# atmel_modular_expansion.net
KiCad netlist of a schematic drawn in EAGLE
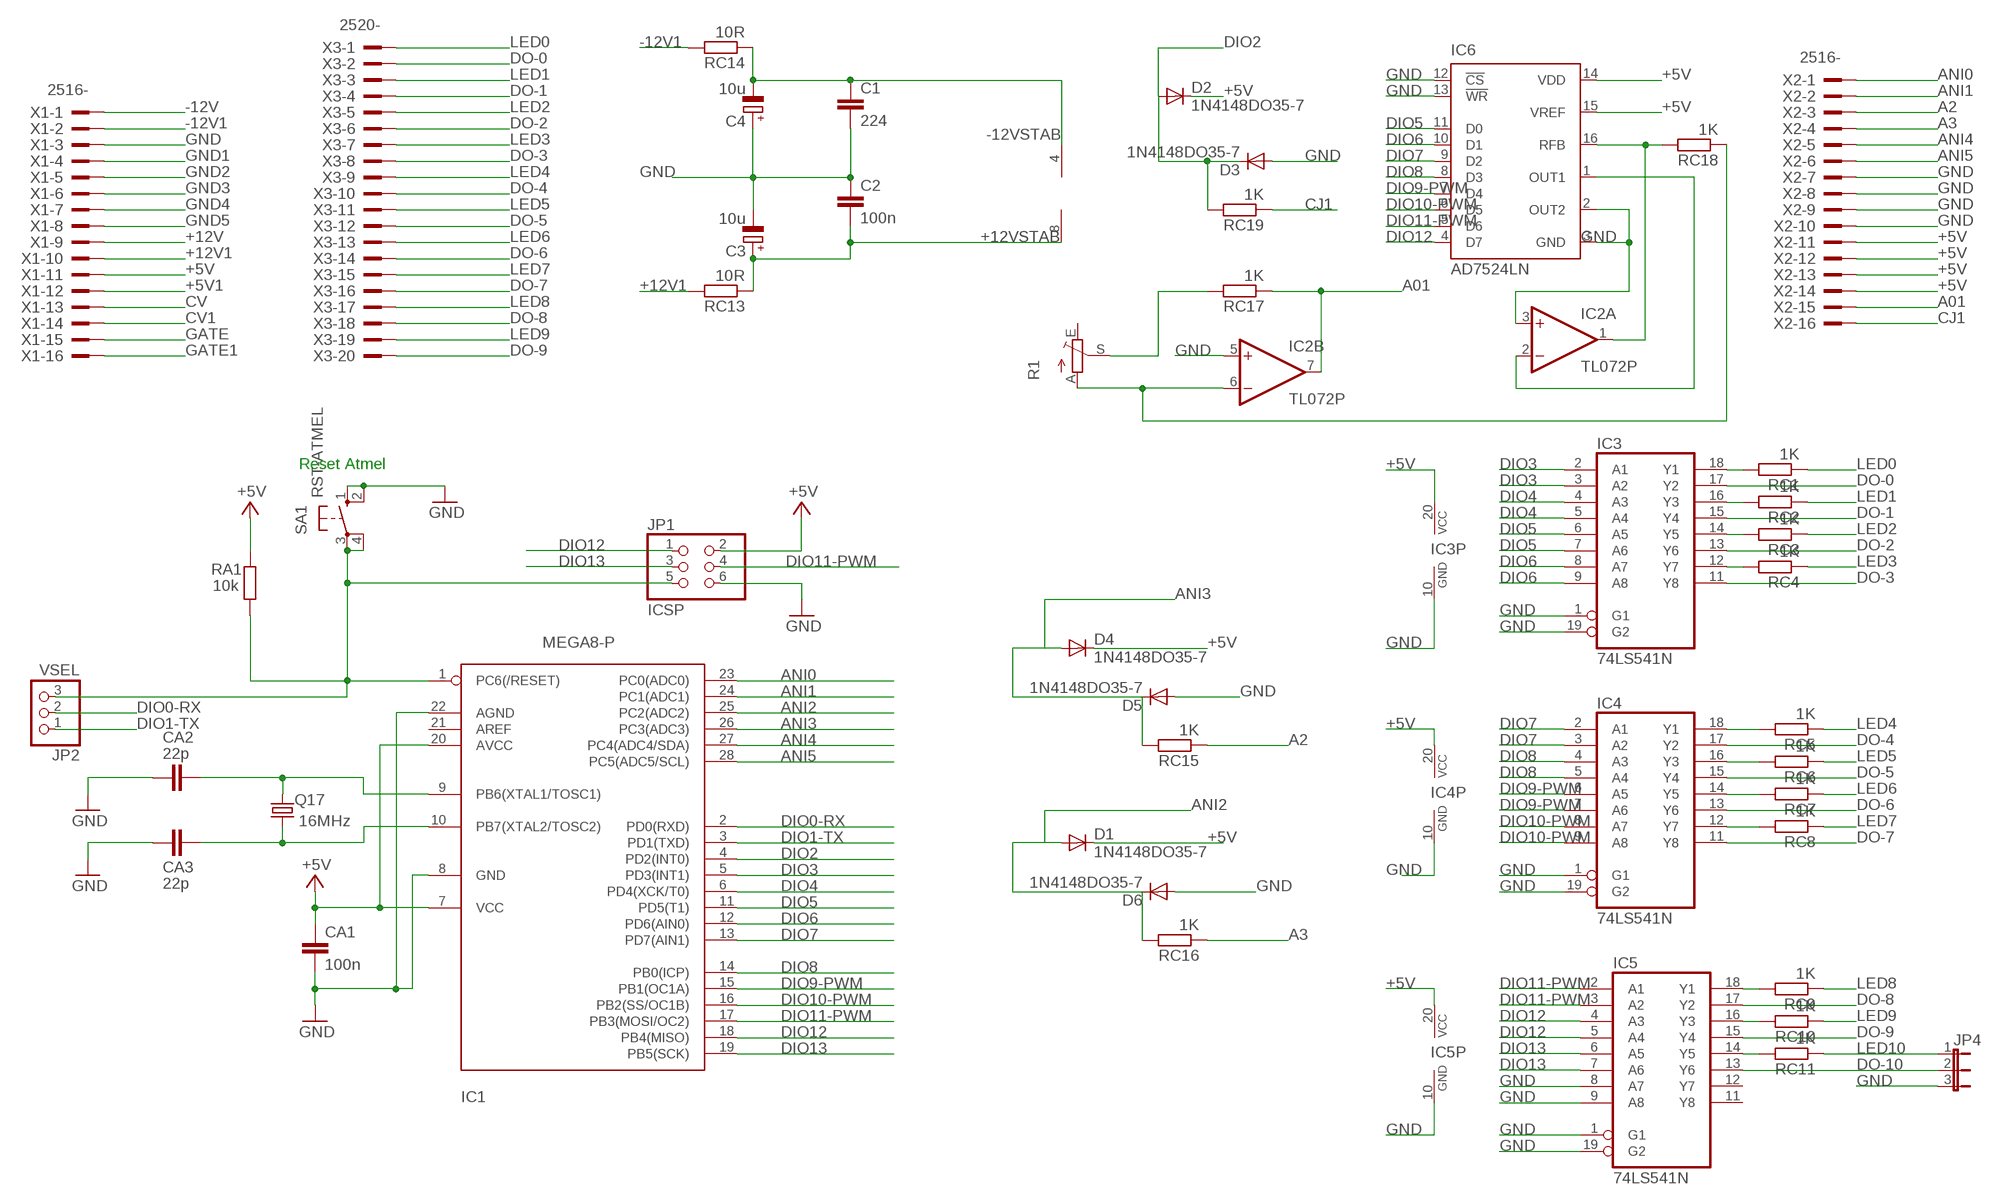
[diagram p0: schematic, sheet 1]

(export (version "E")
  (design (tool "Eeschema 10.0.6"))
  (components
    (comp (ref "C1")
      (value "224")
      (footprint "eagle-import:C050-025X075")
      (libsource (lib "eagle-import") (part "C-EU050-025X075"))
    )
    (comp (ref "C2")
      (value "100n")
      (footprint "eagle-import:C050-025X075")
      (libsource (lib "eagle-import") (part "C-EU050-025X075"))
    )
    (comp (ref "C3")
      (value "10u")
      (footprint "eagle-import:E2,5-7")
      (libsource (lib "eagle-import") (part "CPOL-EUE2.5-7"))
    )
    (comp (ref "C4")
      (value "10u")
      (footprint "eagle-import:E2,5-7")
      (libsource (lib "eagle-import") (part "CPOL-EUE2.5-7"))
    )
    (comp (ref "CA1")
      (value "100n")
      (footprint "eagle-import:C050-025X075")
      (libsource (lib "eagle-import") (part "C-EU050-025X075"))
    )
    (comp (ref "CA2")
      (value "22p")
      (footprint "eagle-import:C050-025X075")
      (libsource (lib "eagle-import") (part "C-EU050-025X075"))
    )
    (comp (ref "CA3")
      (value "22p")
      (footprint "eagle-import:C050-025X075")
      (libsource (lib "eagle-import") (part "C-EU050-025X075"))
    )
    (comp (ref "D1")
      (value "1N4148DO35-7")
      (footprint "eagle-import:DO35-7")
      (libsource (lib "eagle-import") (part "1N4148DO35-7"))
    )
    (comp (ref "D2")
      (value "1N4148DO35-7")
      (footprint "eagle-import:DO35-7")
      (libsource (lib "eagle-import") (part "1N4148DO35-7"))
    )
    (comp (ref "D3")
      (value "1N4148DO35-7")
      (footprint "eagle-import:DO35-7")
      (libsource (lib "eagle-import") (part "1N4148DO35-7"))
    )
    (comp (ref "D4")
      (value "1N4148DO35-7")
      (footprint "eagle-import:DO35-7")
      (libsource (lib "eagle-import") (part "1N4148DO35-7"))
    )
    (comp (ref "D5")
      (value "1N4148DO35-7")
      (footprint "eagle-import:DO35-7")
      (libsource (lib "eagle-import") (part "1N4148DO35-7"))
    )
    (comp (ref "D6")
      (value "1N4148DO35-7")
      (footprint "eagle-import:DO35-7")
      (libsource (lib "eagle-import") (part "1N4148DO35-7"))
    )
    (comp (ref "IC1")
      (value "MEGA8-P")
      (footprint "eagle-import:DIL28-3")
      (libsource (lib "eagle-import") (part "MEGA8-P"))
    )
    (comp (ref "IC2")
      (value "TL072P")
      (footprint "eagle-import:DIL08")
      (libsource (lib "eagle-import") (part "TL072P"))
    )
    (comp (ref "IC3")
      (value "74LS541N")
      (footprint "eagle-import:DIL20")
      (libsource (lib "eagle-import") (part "74541NLS"))
    )
    (comp (ref "IC4")
      (value "74LS541N")
      (footprint "eagle-import:DIL20")
      (libsource (lib "eagle-import") (part "74541NLS"))
    )
    (comp (ref "IC5")
      (value "74LS541N")
      (footprint "eagle-import:DIL20")
      (libsource (lib "eagle-import") (part "74541NLS"))
    )
    (comp (ref "IC6")
      (value "AD7524LN")
      (footprint "eagle-import:DIL16")
      (fields (field (name "MF") "ALTERA CORPORATION") (field (name "MPN") "AD7524LNZ"))
      (libsource (lib "eagle-import") (part "AD7524NL"))
    )
    (comp (ref "JP1")
      (value "ICSP")
      (footprint "eagle-import:2X03")
      (libsource (lib "eagle-import") (part "PINHD-2X3"))
    )
    (comp (ref "JP2")
      (value "VSEL")
      (footprint "eagle-import:1X03")
      (libsource (lib "eagle-import") (part "PINHD-1X3"))
    )
    (comp (ref "JP4")
      (value "JP2E")
      (footprint "eagle-import:JP2")
      (libsource (lib "eagle-import") (part "JP2E"))
    )
    (comp (ref "Q17")
      (value "16MHz")
      (footprint "eagle-import:HC49_S")
      (libsource (lib "eagle-import") (part "CRYSTALHC49S"))
    )
    (comp (ref "R1")
      (value "TRIM_EU-B64Y")
      (footprint "eagle-import:B64Y")
      (libsource (lib "eagle-import") (part "TRIM_EU-B64Y"))
    )
    (comp (ref "RA1")
      (value "10k")
      (footprint "eagle-import:0207_10")
      (libsource (lib "eagle-import") (part "R-EU_0207/10"))
    )
    (comp (ref "RC1")
      (value "1K")
      (footprint "eagle-import:0207_10")
      (libsource (lib "eagle-import") (part "R-EU_0207/10"))
    )
    (comp (ref "RC2")
      (value "1K")
      (footprint "eagle-import:0207_10")
      (libsource (lib "eagle-import") (part "R-EU_0207/10"))
    )
    (comp (ref "RC3")
      (value "1K")
      (footprint "eagle-import:0207_10")
      (libsource (lib "eagle-import") (part "R-EU_0207/10"))
    )
    (comp (ref "RC4")
      (value "1K")
      (footprint "eagle-import:0207_10")
      (libsource (lib "eagle-import") (part "R-EU_0207/10"))
    )
    (comp (ref "RC5")
      (value "1K")
      (footprint "eagle-import:0207_10")
      (libsource (lib "eagle-import") (part "R-EU_0207/10"))
    )
    (comp (ref "RC6")
      (value "1K")
      (footprint "eagle-import:0207_10")
      (libsource (lib "eagle-import") (part "R-EU_0207/10"))
    )
    (comp (ref "RC7")
      (value "1K")
      (footprint "eagle-import:0207_10")
      (libsource (lib "eagle-import") (part "R-EU_0207/10"))
    )
    (comp (ref "RC8")
      (value "1K")
      (footprint "eagle-import:0207_10")
      (libsource (lib "eagle-import") (part "R-EU_0207/10"))
    )
    (comp (ref "RC9")
      (value "1K")
      (footprint "eagle-import:0207_10")
      (libsource (lib "eagle-import") (part "R-EU_0207/10"))
    )
    (comp (ref "RC10")
      (value "1K")
      (footprint "eagle-import:0207_10")
      (libsource (lib "eagle-import") (part "R-EU_0207/10"))
    )
    (comp (ref "RC11")
      (value "1K")
      (footprint "eagle-import:0207_10")
      (libsource (lib "eagle-import") (part "R-EU_0207/10"))
    )
    (comp (ref "RC13")
      (value "10R")
      (footprint "eagle-import:0207_10")
      (libsource (lib "eagle-import") (part "R-EU_0207/10"))
    )
    (comp (ref "RC14")
      (value "10R")
      (footprint "eagle-import:0207_10")
      (libsource (lib "eagle-import") (part "R-EU_0207/10"))
    )
    (comp (ref "RC15")
      (value "1K")
      (footprint "eagle-import:0207_10")
      (libsource (lib "eagle-import") (part "R-EU_0207/10"))
    )
    (comp (ref "RC16")
      (value "1K")
      (footprint "eagle-import:0207_10")
      (libsource (lib "eagle-import") (part "R-EU_0207/10"))
    )
    (comp (ref "RC17")
      (value "1K")
      (footprint "eagle-import:0207_10")
      (libsource (lib "eagle-import") (part "R-EU_0207/10"))
    )
    (comp (ref "RC18")
      (value "1K")
      (footprint "eagle-import:0207_10")
      (libsource (lib "eagle-import") (part "R-EU_0207/10"))
    )
    (comp (ref "RC19")
      (value "1K")
      (footprint "eagle-import:0207_10")
      (libsource (lib "eagle-import") (part "R-EU_0207/10"))
    )
    (comp (ref "SA1")
      (value "RST-ATMEL")
      (footprint "eagle-import:B3F-10XX")
      (libsource (lib "eagle-import") (part "10-XX"))
    )
    (comp (ref "X1")
      (value "2516-")
      (footprint "eagle-import:PAK100_2500-16")
      (libsource (lib "eagle-import") (part "2516-"))
    )
    (comp (ref "X2")
      (value "2516-")
      (footprint "eagle-import:PAK100_2500-16")
      (libsource (lib "eagle-import") (part "2516-"))
    )
    (comp (ref "X3")
      (value "2520-")
      (footprint "eagle-import:PAK100_2500-20")
      (libsource (lib "eagle-import") (part "2520-"))
    )
  )
  (nets
    (net (code "1") (name "+5V") (class "Default")
      (node (ref "CA1") (pin "1") (pinfunction "1_1") (pintype "passive"))
      (node (ref "D1") (pin "C") (pinfunction "C_C") (pintype "passive"))
      (node (ref "D2") (pin "C") (pinfunction "C_C") (pintype "passive"))
      (node (ref "D4") (pin "C") (pinfunction "C_C") (pintype "passive"))
      (node (ref "IC1") (pin "20") (pinfunction "AVCC_20") (pintype "power_in"))
      (node (ref "IC1") (pin "7") (pinfunction "VCC_7") (pintype "power_in"))
      (node (ref "IC3") (pin "20") (pinfunction "VCC_20") (pintype "power_in"))
      (node (ref "IC4") (pin "20") (pinfunction "VCC_20") (pintype "power_in"))
      (node (ref "IC5") (pin "20") (pinfunction "VCC_20") (pintype "power_in"))
      (node (ref "IC6") (pin "14") (pinfunction "VDD_14") (pintype "power_in"))
      (node (ref "IC6") (pin "15") (pinfunction "VREF_15") (pintype "input"))
      (node (ref "JP1") (pin "2") (pinfunction "2_2") (pintype "passive"))
      (node (ref "RA1") (pin "1") (pinfunction "1_1") (pintype "passive"))
      (node (ref "X1") (pin "11") (pinfunction "KL_11") (pintype "passive"))
      (node (ref "X2") (pin "11") (pinfunction "KL_11") (pintype "passive"))
      (node (ref "X2") (pin "12") (pinfunction "KL_12") (pintype "passive"))
      (node (ref "X2") (pin "13") (pinfunction "KL_13") (pintype "passive"))
      (node (ref "X2") (pin "14") (pinfunction "KL_14") (pintype "passive"))
    )
    (net (code "2") (name "/+5V1") (class "Default")
      (node (ref "X1") (pin "12") (pinfunction "KL_12") (pintype "passive"))
    )
    (net (code "3") (name "/+12V") (class "Default")
      (node (ref "X1") (pin "9") (pinfunction "KL_9") (pintype "passive"))
    )
    (net (code "4") (name "/+12V1") (class "Default")
      (node (ref "RC13") (pin "2") (pinfunction "2_2") (pintype "passive"))
      (node (ref "X1") (pin "10") (pinfunction "KL_10") (pintype "passive"))
    )
    (net (code "5") (name "/+12VSTAB") (class "Default")
      (node (ref "C2") (pin "2") (pinfunction "2_2") (pintype "passive"))
      (node (ref "C3") (pin "+") (pinfunction "+_+") (pintype "passive"))
      (node (ref "IC2") (pin "8") (pinfunction "V+_8") (pintype "power_in"))
      (node (ref "RC13") (pin "1") (pinfunction "1_1") (pintype "passive"))
    )
    (net (code "6") (name "/-12V") (class "Default")
      (node (ref "X1") (pin "1") (pinfunction "KL_1") (pintype "passive"))
    )
    (net (code "7") (name "/-12V1") (class "Default")
      (node (ref "RC14") (pin "2") (pinfunction "2_2") (pintype "passive"))
      (node (ref "X1") (pin "2") (pinfunction "KL_2") (pintype "passive"))
    )
    (net (code "8") (name "/-12VSTAB") (class "Default")
      (node (ref "C1") (pin "1") (pinfunction "1_1") (pintype "passive"))
      (node (ref "C4") (pin "-") (pinfunction "-_-") (pintype "passive"))
      (node (ref "IC2") (pin "4") (pinfunction "V-_4") (pintype "power_in"))
      (node (ref "RC14") (pin "1") (pinfunction "1_1") (pintype "passive"))
    )
    (net (code "9") (name "/A01") (class "Default")
      (node (ref "IC2") (pin "7") (pinfunction "OUT_7") (pintype "output"))
      (node (ref "RC17") (pin "1") (pinfunction "1_1") (pintype "passive"))
      (node (ref "X2") (pin "15") (pinfunction "KL_15") (pintype "passive"))
    )
    (net (code "10") (name "/A2") (class "Default")
      (node (ref "RC15") (pin "1") (pinfunction "1_1") (pintype "passive"))
      (node (ref "X2") (pin "3") (pinfunction "KL_3") (pintype "passive"))
    )
    (net (code "11") (name "/A3") (class "Default")
      (node (ref "RC16") (pin "1") (pinfunction "1_1") (pintype "passive"))
      (node (ref "X2") (pin "4") (pinfunction "KL_4") (pintype "passive"))
    )
    (net (code "12") (name "/ANI0") (class "Default")
      (node (ref "IC1") (pin "23") (pinfunction "PC0(ADC0)_23") (pintype "bidirectional"))
      (node (ref "X2") (pin "1") (pinfunction "KL_1") (pintype "passive"))
    )
    (net (code "13") (name "/ANI1") (class "Default")
      (node (ref "IC1") (pin "24") (pinfunction "PC1(ADC1)_24") (pintype "bidirectional"))
      (node (ref "X2") (pin "2") (pinfunction "KL_2") (pintype "passive"))
    )
    (net (code "14") (name "/ANI2") (class "Default")
      (node (ref "D1") (pin "A") (pinfunction "A_A") (pintype "passive"))
      (node (ref "D6") (pin "C") (pinfunction "C_C") (pintype "passive"))
      (node (ref "IC1") (pin "25") (pinfunction "PC2(ADC2)_25") (pintype "bidirectional"))
      (node (ref "RC16") (pin "2") (pinfunction "2_2") (pintype "passive"))
    )
    (net (code "15") (name "/ANI3") (class "Default")
      (node (ref "D4") (pin "A") (pinfunction "A_A") (pintype "passive"))
      (node (ref "D5") (pin "C") (pinfunction "C_C") (pintype "passive"))
      (node (ref "IC1") (pin "26") (pinfunction "PC3(ADC3)_26") (pintype "bidirectional"))
      (node (ref "RC15") (pin "2") (pinfunction "2_2") (pintype "passive"))
    )
    (net (code "16") (name "/ANI4") (class "Default")
      (node (ref "IC1") (pin "27") (pinfunction "PC4(ADC4/SDA)_27") (pintype "bidirectional"))
      (node (ref "X2") (pin "5") (pinfunction "KL_5") (pintype "passive"))
    )
    (net (code "17") (name "/ANI5") (class "Default")
      (node (ref "IC1") (pin "28") (pinfunction "PC5(ADC5/SCL)_28") (pintype "bidirectional"))
      (node (ref "X2") (pin "6") (pinfunction "KL_6") (pintype "passive"))
    )
    (net (code "18") (name "/CJ1") (class "Default")
      (node (ref "RC19") (pin "1") (pinfunction "1_1") (pintype "passive"))
      (node (ref "X2") (pin "16") (pinfunction "KL_16") (pintype "passive"))
    )
    (net (code "19") (name "/CV") (class "Default")
      (node (ref "X1") (pin "13") (pinfunction "KL_13") (pintype "passive"))
    )
    (net (code "20") (name "/CV1") (class "Default")
      (node (ref "X1") (pin "14") (pinfunction "KL_14") (pintype "passive"))
    )
    (net (code "21") (name "/DIO0-RX") (class "Default")
      (node (ref "IC1") (pin "2") (pinfunction "PD0(RXD)_2") (pintype "bidirectional"))
      (node (ref "JP2") (pin "2") (pinfunction "2_2") (pintype "passive"))
    )
    (net (code "22") (name "/DIO1-TX") (class "Default")
      (node (ref "IC1") (pin "3") (pinfunction "PD1(TXD)_3") (pintype "bidirectional"))
      (node (ref "JP2") (pin "1") (pinfunction "1_1") (pintype "passive"))
    )
    (net (code "23") (name "/DIO2") (class "Default")
      (node (ref "D2") (pin "A") (pinfunction "A_A") (pintype "passive"))
      (node (ref "D3") (pin "C") (pinfunction "C_C") (pintype "passive"))
      (node (ref "IC1") (pin "4") (pinfunction "PD2(INT0)_4") (pintype "bidirectional"))
      (node (ref "RC19") (pin "2") (pinfunction "2_2") (pintype "passive"))
    )
    (net (code "24") (name "/DIO3") (class "Default")
      (node (ref "IC1") (pin "5") (pinfunction "PD3(INT1)_5") (pintype "bidirectional"))
      (node (ref "IC3") (pin "2") (pinfunction "A1_2") (pintype "input"))
      (node (ref "IC3") (pin "3") (pinfunction "A2_3") (pintype "input"))
    )
    (net (code "25") (name "/DIO4") (class "Default")
      (node (ref "IC1") (pin "6") (pinfunction "PD4(XCK/T0)_6") (pintype "bidirectional"))
      (node (ref "IC3") (pin "4") (pinfunction "A3_4") (pintype "input"))
      (node (ref "IC3") (pin "5") (pinfunction "A4_5") (pintype "input"))
    )
    (net (code "26") (name "/DIO5") (class "Default")
      (node (ref "IC1") (pin "11") (pinfunction "PD5(T1)_11") (pintype "bidirectional"))
      (node (ref "IC3") (pin "6") (pinfunction "A5_6") (pintype "input"))
      (node (ref "IC3") (pin "7") (pinfunction "A6_7") (pintype "input"))
      (node (ref "IC6") (pin "11") (pinfunction "D0_11") (pintype "input"))
    )
    (net (code "27") (name "/DIO6") (class "Default")
      (node (ref "IC1") (pin "12") (pinfunction "PD6(AIN0)_12") (pintype "bidirectional"))
      (node (ref "IC3") (pin "8") (pinfunction "A7_8") (pintype "input"))
      (node (ref "IC3") (pin "9") (pinfunction "A8_9") (pintype "input"))
      (node (ref "IC6") (pin "10") (pinfunction "D1_10") (pintype "input"))
    )
    (net (code "28") (name "/DIO7") (class "Default")
      (node (ref "IC1") (pin "13") (pinfunction "PD7(AIN1)_13") (pintype "bidirectional"))
      (node (ref "IC4") (pin "2") (pinfunction "A1_2") (pintype "input"))
      (node (ref "IC4") (pin "3") (pinfunction "A2_3") (pintype "input"))
      (node (ref "IC6") (pin "9") (pinfunction "D2_9") (pintype "input"))
    )
    (net (code "29") (name "/DIO8") (class "Default")
      (node (ref "IC1") (pin "14") (pinfunction "PB0(ICP)_14") (pintype "bidirectional"))
      (node (ref "IC4") (pin "4") (pinfunction "A3_4") (pintype "input"))
      (node (ref "IC4") (pin "5") (pinfunction "A4_5") (pintype "input"))
      (node (ref "IC6") (pin "8") (pinfunction "D3_8") (pintype "input"))
    )
    (net (code "30") (name "/DIO9-PWM") (class "Default")
      (node (ref "IC1") (pin "15") (pinfunction "PB1(OC1A)_15") (pintype "bidirectional"))
      (node (ref "IC4") (pin "6") (pinfunction "A5_6") (pintype "input"))
      (node (ref "IC4") (pin "7") (pinfunction "A6_7") (pintype "input"))
      (node (ref "IC6") (pin "7") (pinfunction "D4_7") (pintype "input"))
    )
    (net (code "31") (name "/DIO10-PWM") (class "Default")
      (node (ref "IC1") (pin "16") (pinfunction "PB2(SS/OC1B)_16") (pintype "bidirectional"))
      (node (ref "IC4") (pin "8") (pinfunction "A7_8") (pintype "input"))
      (node (ref "IC4") (pin "9") (pinfunction "A8_9") (pintype "input"))
      (node (ref "IC6") (pin "6") (pinfunction "D5_6") (pintype "input"))
    )
    (net (code "32") (name "/DIO11-PWM") (class "Default")
      (node (ref "IC1") (pin "17") (pinfunction "PB3(MOSI/OC2)_17") (pintype "bidirectional"))
      (node (ref "IC5") (pin "2") (pinfunction "A1_2") (pintype "input"))
      (node (ref "IC5") (pin "3") (pinfunction "A2_3") (pintype "input"))
      (node (ref "IC6") (pin "5") (pinfunction "D6_5") (pintype "input"))
      (node (ref "JP1") (pin "4") (pinfunction "4_4") (pintype "passive"))
    )
    (net (code "33") (name "/DIO12") (class "Default")
      (node (ref "IC1") (pin "18") (pinfunction "PB4(MISO)_18") (pintype "bidirectional"))
      (node (ref "IC5") (pin "4") (pinfunction "A3_4") (pintype "input"))
      (node (ref "IC5") (pin "5") (pinfunction "A4_5") (pintype "input"))
      (node (ref "IC6") (pin "4") (pinfunction "D7_4") (pintype "input"))
      (node (ref "JP1") (pin "1") (pinfunction "1_1") (pintype "passive"))
    )
    (net (code "34") (name "/DIO13") (class "Default")
      (node (ref "IC1") (pin "19") (pinfunction "PB5(SCK)_19") (pintype "bidirectional"))
      (node (ref "IC5") (pin "6") (pinfunction "A5_6") (pintype "input"))
      (node (ref "IC5") (pin "7") (pinfunction "A6_7") (pintype "input"))
      (node (ref "JP1") (pin "3") (pinfunction "3_3") (pintype "passive"))
    )
    (net (code "35") (name "/DO-0") (class "Default")
      (node (ref "IC3") (pin "17") (pinfunction "Y2_17") (pintype "tri_state"))
      (node (ref "X3") (pin "2") (pinfunction "KL_2") (pintype "passive"))
    )
    (net (code "36") (name "/DO-1") (class "Default")
      (node (ref "IC3") (pin "15") (pinfunction "Y4_15") (pintype "tri_state"))
      (node (ref "X3") (pin "4") (pinfunction "KL_4") (pintype "passive"))
    )
    (net (code "37") (name "/DO-2") (class "Default")
      (node (ref "IC3") (pin "13") (pinfunction "Y6_13") (pintype "tri_state"))
      (node (ref "X3") (pin "6") (pinfunction "KL_6") (pintype "passive"))
    )
    (net (code "38") (name "/DO-3") (class "Default")
      (node (ref "IC3") (pin "11") (pinfunction "Y8_11") (pintype "tri_state"))
      (node (ref "X3") (pin "8") (pinfunction "KL_8") (pintype "passive"))
    )
    (net (code "39") (name "/DO-4") (class "Default")
      (node (ref "IC4") (pin "17") (pinfunction "Y2_17") (pintype "tri_state"))
      (node (ref "X3") (pin "10") (pinfunction "KL_10") (pintype "passive"))
    )
    (net (code "40") (name "/DO-5") (class "Default")
      (node (ref "IC4") (pin "15") (pinfunction "Y4_15") (pintype "tri_state"))
      (node (ref "X3") (pin "12") (pinfunction "KL_12") (pintype "passive"))
    )
    (net (code "41") (name "/DO-6") (class "Default")
      (node (ref "IC4") (pin "13") (pinfunction "Y6_13") (pintype "tri_state"))
      (node (ref "X3") (pin "14") (pinfunction "KL_14") (pintype "passive"))
    )
    (net (code "42") (name "/DO-7") (class "Default")
      (node (ref "IC4") (pin "11") (pinfunction "Y8_11") (pintype "tri_state"))
      (node (ref "X3") (pin "16") (pinfunction "KL_16") (pintype "passive"))
    )
    (net (code "43") (name "/DO-8") (class "Default")
      (node (ref "IC5") (pin "17") (pinfunction "Y2_17") (pintype "tri_state"))
      (node (ref "X3") (pin "18") (pinfunction "KL_18") (pintype "passive"))
    )
    (net (code "44") (name "/DO-9") (class "Default")
      (node (ref "IC5") (pin "15") (pinfunction "Y4_15") (pintype "tri_state"))
      (node (ref "X3") (pin "20") (pinfunction "KL_20") (pintype "passive"))
    )
    (net (code "45") (name "/DO-10") (class "Default")
      (node (ref "IC5") (pin "13") (pinfunction "Y6_13") (pintype "tri_state"))
      (node (ref "JP4") (pin "2") (pinfunction "2_2") (pintype "passive"))
    )
    (net (code "46") (name "/GATE") (class "Default")
      (node (ref "X1") (pin "15") (pinfunction "KL_15") (pintype "passive"))
    )
    (net (code "47") (name "/GATE1") (class "Default")
      (node (ref "X1") (pin "16") (pinfunction "KL_16") (pintype "passive"))
    )
    (net (code "48") (name "/GND1") (class "Default")
      (node (ref "X1") (pin "4") (pinfunction "KL_4") (pintype "passive"))
    )
    (net (code "49") (name "/GND2") (class "Default")
      (node (ref "X1") (pin "5") (pinfunction "KL_5") (pintype "passive"))
    )
    (net (code "50") (name "/GND3") (class "Default")
      (node (ref "X1") (pin "6") (pinfunction "KL_6") (pintype "passive"))
    )
    (net (code "51") (name "/GND4") (class "Default")
      (node (ref "X1") (pin "7") (pinfunction "KL_7") (pintype "passive"))
    )
    (net (code "52") (name "/GND5") (class "Default")
      (node (ref "X1") (pin "8") (pinfunction "KL_8") (pintype "passive"))
    )
    (net (code "53") (name "/LED0") (class "Default")
      (node (ref "RC1") (pin "1") (pinfunction "1_1") (pintype "passive"))
      (node (ref "X3") (pin "1") (pinfunction "KL_1") (pintype "passive"))
    )
    (net (code "54") (name "/LED1") (class "Default")
      (node (ref "RC2") (pin "1") (pinfunction "1_1") (pintype "passive"))
      (node (ref "X3") (pin "3") (pinfunction "KL_3") (pintype "passive"))
    )
    (net (code "55") (name "/LED2") (class "Default")
      (node (ref "RC3") (pin "1") (pinfunction "1_1") (pintype "passive"))
      (node (ref "X3") (pin "5") (pinfunction "KL_5") (pintype "passive"))
    )
    (net (code "56") (name "/LED3") (class "Default")
      (node (ref "RC4") (pin "1") (pinfunction "1_1") (pintype "passive"))
      (node (ref "X3") (pin "7") (pinfunction "KL_7") (pintype "passive"))
    )
    (net (code "57") (name "/LED4") (class "Default")
      (node (ref "RC5") (pin "1") (pinfunction "1_1") (pintype "passive"))
      (node (ref "X3") (pin "9") (pinfunction "KL_9") (pintype "passive"))
    )
    (net (code "58") (name "/LED5") (class "Default")
      (node (ref "RC6") (pin "1") (pinfunction "1_1") (pintype "passive"))
      (node (ref "X3") (pin "11") (pinfunction "KL_11") (pintype "passive"))
    )
    (net (code "59") (name "/LED6") (class "Default")
      (node (ref "RC7") (pin "1") (pinfunction "1_1") (pintype "passive"))
      (node (ref "X3") (pin "13") (pinfunction "KL_13") (pintype "passive"))
    )
    (net (code "60") (name "/LED7") (class "Default")
      (node (ref "RC8") (pin "1") (pinfunction "1_1") (pintype "passive"))
      (node (ref "X3") (pin "15") (pinfunction "KL_15") (pintype "passive"))
    )
    (net (code "61") (name "/LED8") (class "Default")
      (node (ref "RC9") (pin "1") (pinfunction "1_1") (pintype "passive"))
      (node (ref "X3") (pin "17") (pinfunction "KL_17") (pintype "passive"))
    )
    (net (code "62") (name "/LED9") (class "Default")
      (node (ref "RC10") (pin "1") (pinfunction "1_1") (pintype "passive"))
      (node (ref "X3") (pin "19") (pinfunction "KL_19") (pintype "passive"))
    )
    (net (code "63") (name "/LED10") (class "Default")
      (node (ref "JP4") (pin "1") (pinfunction "1_1") (pintype "passive"))
      (node (ref "RC11") (pin "1") (pinfunction "1_1") (pintype "passive"))
    )
    (net (code "64") (name "GND") (class "Default")
      (node (ref "C1") (pin "2") (pinfunction "2_2") (pintype "passive"))
      (node (ref "C2") (pin "1") (pinfunction "1_1") (pintype "passive"))
      (node (ref "C3") (pin "-") (pinfunction "-_-") (pintype "passive"))
      (node (ref "C4") (pin "+") (pinfunction "+_+") (pintype "passive"))
      (node (ref "CA1") (pin "2") (pinfunction "2_2") (pintype "passive"))
      (node (ref "CA2") (pin "2") (pinfunction "2_2") (pintype "passive"))
      (node (ref "CA3") (pin "2") (pinfunction "2_2") (pintype "passive"))
      (node (ref "D3") (pin "A") (pinfunction "A_A") (pintype "passive"))
      (node (ref "D5") (pin "A") (pinfunction "A_A") (pintype "passive"))
      (node (ref "D6") (pin "A") (pinfunction "A_A") (pintype "passive"))
      (node (ref "IC1") (pin "22") (pinfunction "AGND_22") (pintype "power_in"))
      (node (ref "IC1") (pin "8") (pinfunction "GND_8") (pintype "power_in"))
      (node (ref "IC2") (pin "3") (pinfunction "+IN_3") (pintype "input"))
      (node (ref "IC2") (pin "5") (pinfunction "+IN_5") (pintype "input"))
      (node (ref "IC3") (pin "1") (pinfunction "G1_1") (pintype "input"))
      (node (ref "IC3") (pin "10") (pinfunction "GND_10") (pintype "power_in"))
      (node (ref "IC3") (pin "19") (pinfunction "G2_19") (pintype "input"))
      (node (ref "IC4") (pin "1") (pinfunction "G1_1") (pintype "input"))
      (node (ref "IC4") (pin "10") (pinfunction "GND_10") (pintype "power_in"))
      (node (ref "IC4") (pin "19") (pinfunction "G2_19") (pintype "input"))
      (node (ref "IC5") (pin "1") (pinfunction "G1_1") (pintype "input"))
      (node (ref "IC5") (pin "10") (pinfunction "GND_10") (pintype "power_in"))
      (node (ref "IC5") (pin "19") (pinfunction "G2_19") (pintype "input"))
      (node (ref "IC5") (pin "8") (pinfunction "A7_8") (pintype "input"))
      (node (ref "IC5") (pin "9") (pinfunction "A8_9") (pintype "input"))
      (node (ref "IC6") (pin "12") (pinfunction "~{CS}_12") (pintype "input"))
      (node (ref "IC6") (pin "13") (pinfunction "~{WR}_13") (pintype "input"))
      (node (ref "IC6") (pin "2") (pinfunction "OUT2_2") (pintype "passive"))
      (node (ref "IC6") (pin "3") (pinfunction "GND_3") (pintype "power_in"))
      (node (ref "JP1") (pin "6") (pinfunction "6_6") (pintype "passive"))
      (node (ref "JP4") (pin "3") (pinfunction "3_3") (pintype "passive"))
      (node (ref "SA1") (pin "1") (pinfunction "S_1") (pintype "passive"))
      (node (ref "SA1") (pin "2") (pinfunction "S1_2") (pintype "passive"))
      (node (ref "X1") (pin "3") (pinfunction "KL_3") (pintype "passive"))
      (node (ref "X2") (pin "10") (pinfunction "KL_10") (pintype "passive"))
      (node (ref "X2") (pin "7") (pinfunction "KL_7") (pintype "passive"))
      (node (ref "X2") (pin "8") (pinfunction "KL_8") (pintype "passive"))
      (node (ref "X2") (pin "9") (pinfunction "KL_9") (pintype "passive"))
    )
    (net (code "65") (name "Net-(IC1-PB6(XTAL1{slash}TOSC1))") (class "Default")
      (node (ref "CA2") (pin "1") (pinfunction "1_1") (pintype "passive"))
      (node (ref "IC1") (pin "9") (pinfunction "PB6(XTAL1/TOSC1)_9") (pintype "bidirectional"))
      (node (ref "Q17") (pin "2") (pinfunction "2_2") (pintype "passive"))
    )
    (net (code "66") (name "Net-(IC1-PB7(XTAL2{slash}TOSC2))") (class "Default")
      (node (ref "CA3") (pin "1") (pinfunction "1_1") (pintype "passive"))
      (node (ref "IC1") (pin "10") (pinfunction "PB7(XTAL2/TOSC2)_10") (pintype "bidirectional"))
      (node (ref "Q17") (pin "1") (pinfunction "1_1") (pintype "passive"))
    )
    (net (code "67") (name "Net-(IC1-PC6({slash}RESET))") (class "Default")
      (node (ref "IC1") (pin "1") (pinfunction "PC6(/RESET)_1") (pintype "bidirectional"))
      (node (ref "JP1") (pin "5") (pinfunction "5_5") (pintype "passive"))
      (node (ref "JP2") (pin "3") (pinfunction "3_3") (pintype "passive"))
      (node (ref "RA1") (pin "2") (pinfunction "2_2") (pintype "passive"))
      (node (ref "SA1") (pin "3") (pinfunction "P_3") (pintype "passive"))
      (node (ref "SA1") (pin "4") (pinfunction "P1_4") (pintype "passive"))
    )
    (net (code "68") (name "Net-(IC2A--IN)") (class "Default")
      (node (ref "IC2") (pin "2") (pinfunction "-IN_2") (pintype "input"))
      (node (ref "IC6") (pin "1") (pinfunction "OUT1_1") (pintype "passive"))
    )
    (net (code "69") (name "Net-(IC2A-OUT)") (class "Default")
      (node (ref "IC2") (pin "1") (pinfunction "OUT_1") (pintype "output"))
      (node (ref "IC6") (pin "16") (pinfunction "RFB_16") (pintype "passive"))
      (node (ref "RC18") (pin "2") (pinfunction "2_2") (pintype "passive"))
    )
    (net (code "70") (name "Net-(IC2B--IN)") (class "Default")
      (node (ref "IC2") (pin "6") (pinfunction "-IN_6") (pintype "input"))
      (node (ref "R1") (pin "A") (pinfunction "A_A") (pintype "passive"))
      (node (ref "RC18") (pin "1") (pinfunction "1_1") (pintype "passive"))
    )
    (net (code "71") (name "Net-(IC3A-Y1)") (class "Default")
      (node (ref "IC3") (pin "18") (pinfunction "Y1_18") (pintype "tri_state"))
      (node (ref "RC1") (pin "2") (pinfunction "2_2") (pintype "passive"))
    )
    (net (code "72") (name "Net-(IC3A-Y3)") (class "Default")
      (node (ref "IC3") (pin "16") (pinfunction "Y3_16") (pintype "tri_state"))
      (node (ref "RC2") (pin "2") (pinfunction "2_2") (pintype "passive"))
    )
    (net (code "73") (name "Net-(IC3A-Y5)") (class "Default")
      (node (ref "IC3") (pin "14") (pinfunction "Y5_14") (pintype "tri_state"))
      (node (ref "RC3") (pin "2") (pinfunction "2_2") (pintype "passive"))
    )
    (net (code "74") (name "Net-(IC3A-Y7)") (class "Default")
      (node (ref "IC3") (pin "12") (pinfunction "Y7_12") (pintype "tri_state"))
      (node (ref "RC4") (pin "2") (pinfunction "2_2") (pintype "passive"))
    )
    (net (code "75") (name "Net-(IC4A-Y1)") (class "Default")
      (node (ref "IC4") (pin "18") (pinfunction "Y1_18") (pintype "tri_state"))
      (node (ref "RC5") (pin "2") (pinfunction "2_2") (pintype "passive"))
    )
    (net (code "76") (name "Net-(IC4A-Y3)") (class "Default")
      (node (ref "IC4") (pin "16") (pinfunction "Y3_16") (pintype "tri_state"))
      (node (ref "RC6") (pin "2") (pinfunction "2_2") (pintype "passive"))
    )
    (net (code "77") (name "Net-(IC4A-Y5)") (class "Default")
      (node (ref "IC4") (pin "14") (pinfunction "Y5_14") (pintype "tri_state"))
      (node (ref "RC7") (pin "2") (pinfunction "2_2") (pintype "passive"))
    )
    (net (code "78") (name "Net-(IC4A-Y7)") (class "Default")
      (node (ref "IC4") (pin "12") (pinfunction "Y7_12") (pintype "tri_state"))
      (node (ref "RC8") (pin "2") (pinfunction "2_2") (pintype "passive"))
    )
    (net (code "79") (name "Net-(IC5A-Y1)") (class "Default")
      (node (ref "IC5") (pin "18") (pinfunction "Y1_18") (pintype "tri_state"))
      (node (ref "RC9") (pin "2") (pinfunction "2_2") (pintype "passive"))
    )
    (net (code "80") (name "Net-(IC5A-Y3)") (class "Default")
      (node (ref "IC5") (pin "16") (pinfunction "Y3_16") (pintype "tri_state"))
      (node (ref "RC10") (pin "2") (pinfunction "2_2") (pintype "passive"))
    )
    (net (code "81") (name "Net-(IC5A-Y5)") (class "Default")
      (node (ref "IC5") (pin "14") (pinfunction "Y5_14") (pintype "tri_state"))
      (node (ref "RC11") (pin "2") (pinfunction "2_2") (pintype "passive"))
    )
    (net (code "82") (name "Net-(R1-PadS)") (class "Default")
      (node (ref "R1") (pin "S") (pinfunction "S_S") (pintype "passive"))
      (node (ref "RC17") (pin "2") (pinfunction "2_2") (pintype "passive"))
    )
    (net (code "83") (name "unconnected-(IC1-AREF-Pad21)") (class "Default")
      (node (ref "IC1") (pin "21") (pinfunction "AREF_21") (pintype "passive"))
    )
    (net (code "84") (name "unconnected-(IC5A-Y7-Pad12)") (class "Default")
      (node (ref "IC5") (pin "12") (pinfunction "Y7_12") (pintype "tri_state"))
    )
    (net (code "85") (name "unconnected-(IC5A-Y8-Pad11)") (class "Default")
      (node (ref "IC5") (pin "11") (pinfunction "Y8_11") (pintype "tri_state"))
    )
    (net (code "86") (name "unconnected-(R1-PadE)") (class "Default")
      (node (ref "R1") (pin "E") (pinfunction "E_E") (pintype "passive"))
    )
  )
)
